# power.net
KiCad netlist of a schematic drawn in Altium Designer
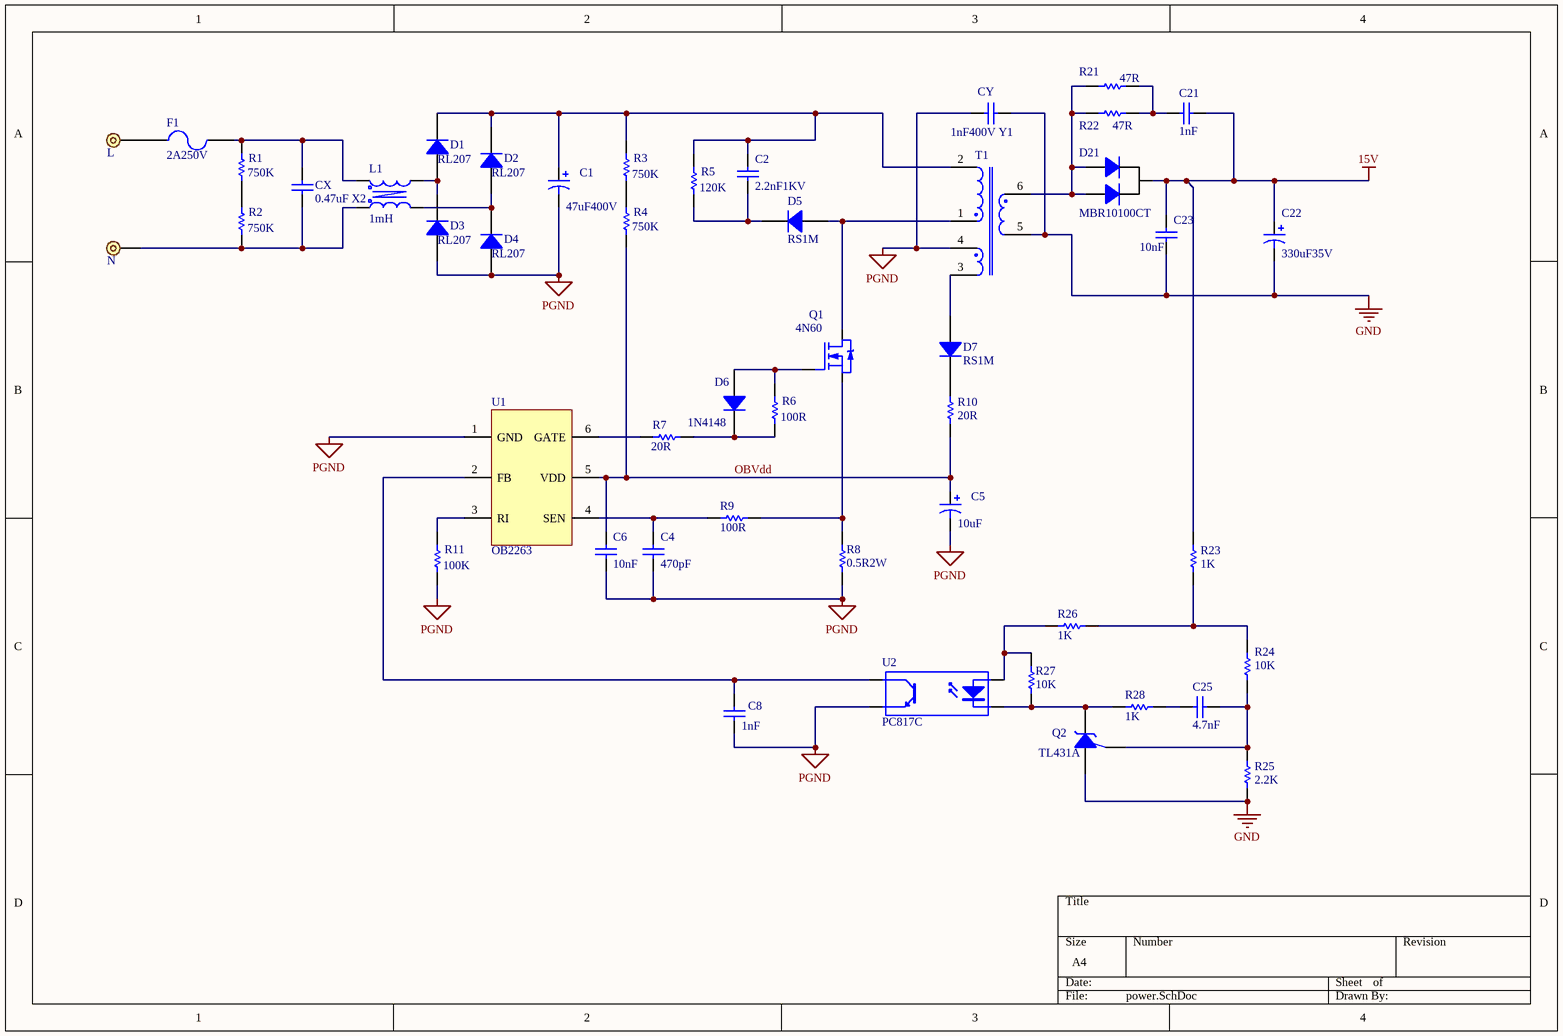
[diagram p0: power.SchDoc]

(export (version "E")
  (design (tool "Eeschema 10.0.6"))
  (components
    (comp (ref "C1")
      (value "47uF400V")
      (footprint "CAP16x25")
      (description "电解电容")
      (fields (field (name "PUBLISHER") "Altium Limited"))
      (libsource (lib "nizn") (part "Cap Pol2"))
    )
    (comp (ref "C2")
      (value "2.2nF1KV")
      (footprint "CAP5")
      (description "涤纶电容")
      (fields (field (name "Comment") "Cap") (field (name "PUBLISHER") "Altium Limited"))
      (libsource (lib "Miscellaneous Devices") (part "Cap"))
    )
    (comp (ref "C4")
      (value "470pF")
      (footprint "CAP0805")
      (description "贴片电容")
      (fields (field (name "Comment") "Cap") (field (name "PUBLISHER") "Altium Limited"))
      (libsource (lib "Miscellaneous Devices") (part "Cap"))
    )
    (comp (ref "C5")
      (value "10uF")
      (footprint "CAP3")
      (description "电解电容")
      (fields (field (name "PUBLISHER") "Altium Limited"))
      (libsource (lib "nizn") (part "Cap Pol2"))
    )
    (comp (ref "C6")
      (value "10nF")
      (footprint "CAP0805")
      (description "贴片电容")
      (fields (field (name "Comment") "Cap") (field (name "PUBLISHER") "Altium Limited"))
      (libsource (lib "Miscellaneous Devices") (part "Cap"))
    )
    (comp (ref "C8")
      (value "1nF")
      (footprint "CAP0805")
      (description "贴片电容")
      (fields (field (name "Comment") "Cap") (field (name "PUBLISHER") "Altium Limited"))
      (libsource (lib "Miscellaneous Devices") (part "Cap"))
    )
    (comp (ref "C21")
      (value "1nF")
      (footprint "CAP1206")
      (description "贴片电容")
      (fields (field (name "Comment") "Cap") (field (name "PUBLISHER") "Altium Limited"))
      (libsource (lib "Miscellaneous Devices") (part "Cap"))
    )
    (comp (ref "C22")
      (value "330uF35V")
      (footprint "CAP10X16")
      (description "电解电容")
      (fields (field (name "PUBLISHER") "Altium Limited"))
      (libsource (lib "nizn") (part "Cap Pol2"))
    )
    (comp (ref "C23")
      (value "10nF")
      (footprint "CAP0805")
      (description "贴片电容")
      (fields (field (name "Comment") "Cap") (field (name "PUBLISHER") "Altium Limited"))
      (libsource (lib "Miscellaneous Devices") (part "Cap"))
    )
    (comp (ref "C25")
      (value "4.7nF")
      (footprint "CAP0805")
      (description "贴片电容")
      (fields (field (name "Comment") "Cap") (field (name "PUBLISHER") "Altium Limited"))
      (libsource (lib "Miscellaneous Devices") (part "Cap"))
    )
    (comp (ref "CX")
      (value "0.47uF X2")
      (footprint "CAPX2")
      (description "X2 安规电容")
      (fields (field (name "Comment") "Cap") (field (name "PUBLISHER") "Altium Limited"))
      (libsource (lib "Miscellaneous Devices") (part "Cap"))
    )
    (comp (ref "CY")
      (value "1nF400V Y1")
      (footprint "CAPY2")
      (description "Y2 安规电容")
      (fields (field (name "Comment") "Cap") (field (name "PUBLISHER") "Altium Limited"))
      (libsource (lib "Miscellaneous Devices") (part "Cap"))
    )
    (comp (ref "D1")
      (value "RL207")
      (footprint "DIO10mm")
      (description "直插二极管")
      (fields (field (name "PUBLISHER") "Altium Limited"))
      (libsource (lib "nizn") (part "Diode"))
    )
    (comp (ref "D2")
      (value "RL207")
      (footprint "DIO10mm")
      (description "直插二极管")
      (fields (field (name "PUBLISHER") "Altium Limited"))
      (libsource (lib "nizn") (part "Diode"))
    )
    (comp (ref "D3")
      (value "RL207")
      (footprint "DIO10mm")
      (description "直插二极管")
      (fields (field (name "PUBLISHER") "Altium Limited"))
      (libsource (lib "nizn") (part "Diode"))
    )
    (comp (ref "D4")
      (value "RL207")
      (footprint "DIO10mm")
      (description "直插二极管")
      (fields (field (name "PUBLISHER") "Altium Limited"))
      (libsource (lib "nizn") (part "Diode"))
    )
    (comp (ref "D5")
      (value "RS1M")
      (footprint "DO214A")
      (description "贴片二极管")
      (fields (field (name "PUBLISHER") "Altium Limited"))
      (libsource (lib "nizn") (part "Diode"))
    )
    (comp (ref "D6")
      (value "1N4148")
      (footprint "1N4148SMT")
      (description "贴片二极管")
      (fields (field (name "PUBLISHER") "Altium Limited"))
      (libsource (lib "nizn") (part "Diode"))
    )
    (comp (ref "D7")
      (value "RS1M")
      (footprint "DO214A")
      (description "贴片二极管")
      (fields (field (name "PUBLISHER") "Altium Limited"))
      (libsource (lib "nizn") (part "Diode"))
    )
    (comp (ref "D21")
      (value "MBR10100CT")
      (footprint "TO220DIO_HS")
      (description "整流双二极管")
      (fields (field (name "PUBLISHER") "Altium Limited"))
      (libsource (lib "nizn") (part "Diode2"))
    )
    (comp (ref "F1")
      (value "2A250V")
      (footprint "FUSE3X10_2")
      (description "直插保险丝")
      (fields (field (name "PUBLISHER") "Altium Limited"))
      (libsource (lib "nizn") (part "Fuse 2"))
    )
    (comp (ref "J1")
      (value "L")
      (footprint "PAD1")
      (description "电源火线")
      (fields (field (name "PUBLISHER") "Altium Limited"))
      (libsource (lib "nizn") (part "Header1"))
    )
    (comp (ref "J2")
      (value "N")
      (footprint "PAD1")
      (description "电源零线")
      (fields (field (name "PUBLISHER") "Altium Limited"))
      (libsource (lib "nizn") (part "Header1"))
    )
    (comp (ref "L1")
      (value "1mH")
      (footprint "BU10")
      (description "共模电感")
      (libsource (lib "nizn") (part "TRANS3"))
    )
    (comp (ref "Q1")
      (value "4N60")
      (footprint "TO220MOS_HS")
      (description "高压 NMOS")
      (fields (field (name "PUBLISHER") "Altium Limited"))
      (libsource (lib "nizn") (part "NMOS"))
    )
    (comp (ref "Q2")
      (value "TL431A")
      (footprint "SOT23_431")
      (description "基准集成电路")
      (fields (field (name "PUBLISHER") "Altium Limited"))
      (libsource (lib "nizn") (part "TL431"))
    )
    (comp (ref "R1")
      (value "750K")
      (footprint "RES1206")
      (description "贴片电阻")
      (fields (field (name "Comment") "Res1") (field (name "PUBLISHER") "Altium Limited"))
      (libsource (lib "Miscellaneous Devices") (part "Res1"))
    )
    (comp (ref "R2")
      (value "750K")
      (footprint "RES1206")
      (description "贴片电阻")
      (fields (field (name "Comment") "Res1") (field (name "PUBLISHER") "Altium Limited"))
      (libsource (lib "Miscellaneous Devices") (part "Res1"))
    )
    (comp (ref "R3")
      (value "750K")
      (footprint "RES1206")
      (description "贴片电阻")
      (fields (field (name "Comment") "Res1") (field (name "PUBLISHER") "Altium Limited"))
      (libsource (lib "Miscellaneous Devices") (part "Res1"))
    )
    (comp (ref "R4")
      (value "750K")
      (footprint "RES1206")
      (description "贴片电阻")
      (fields (field (name "Comment") "Res1") (field (name "PUBLISHER") "Altium Limited"))
      (libsource (lib "Miscellaneous Devices") (part "Res1"))
    )
    (comp (ref "R5")
      (value "120K")
      (footprint "RES1206")
      (description "贴片电阻")
      (fields (field (name "Comment") "Res1") (field (name "PUBLISHER") "Altium Limited"))
      (libsource (lib "Miscellaneous Devices") (part "Res1"))
    )
    (comp (ref "R6")
      (value "100R")
      (footprint "RES0805")
      (description "贴片电阻")
      (fields (field (name "Comment") "Res1") (field (name "PUBLISHER") "Altium Limited"))
      (libsource (lib "Miscellaneous Devices") (part "Res1"))
    )
    (comp (ref "R7")
      (value "20R")
      (footprint "RES0805")
      (description "贴片电阻")
      (fields (field (name "Comment") "Res1") (field (name "PUBLISHER") "Altium Limited"))
      (libsource (lib "Miscellaneous Devices") (part "Res1"))
    )
    (comp (ref "R8")
      (value "0.5R2W")
      (footprint "RES2W")
      (description "2W 直插电阻")
      (fields (field (name "Comment") "Res1") (field (name "PUBLISHER") "Altium Limited"))
      (libsource (lib "Miscellaneous Devices") (part "Res1"))
    )
    (comp (ref "R9")
      (value "100R")
      (footprint "RES0805")
      (description "贴片电阻")
      (fields (field (name "Comment") "Res1") (field (name "PUBLISHER") "Altium Limited"))
      (libsource (lib "Miscellaneous Devices") (part "Res1"))
    )
    (comp (ref "R10")
      (value "20R")
      (footprint "RES1206")
      (description "贴片电阻")
      (fields (field (name "Comment") "Res1") (field (name "PUBLISHER") "Altium Limited"))
      (libsource (lib "Miscellaneous Devices") (part "Res1"))
    )
    (comp (ref "R11")
      (value "100K")
      (footprint "RES0805")
      (description "贴片电阻")
      (fields (field (name "Comment") "Res1") (field (name "PUBLISHER") "Altium Limited"))
      (libsource (lib "Miscellaneous Devices") (part "Res1"))
    )
    (comp (ref "R21")
      (value "47R")
      (footprint "RES1206")
      (description "贴片电阻")
      (fields (field (name "Comment") "Res1") (field (name "PUBLISHER") "Altium Limited"))
      (libsource (lib "Miscellaneous Devices") (part "Res1"))
    )
    (comp (ref "R22")
      (value "47R")
      (footprint "RES1206")
      (description "贴片电阻")
      (fields (field (name "Comment") "Res1") (field (name "PUBLISHER") "Altium Limited"))
      (libsource (lib "Miscellaneous Devices") (part "Res1"))
    )
    (comp (ref "R23")
      (value "1K")
      (footprint "RES0805")
      (description "贴片电阻")
      (fields (field (name "Comment") "Res1") (field (name "PUBLISHER") "Altium Limited"))
      (libsource (lib "Miscellaneous Devices") (part "Res1"))
    )
    (comp (ref "R24")
      (value "10K")
      (footprint "RES0805")
      (description "贴片电阻")
      (fields (field (name "Comment") "Res1") (field (name "PUBLISHER") "Altium Limited"))
      (libsource (lib "Miscellaneous Devices") (part "Res1"))
    )
    (comp (ref "R25")
      (value "2.2K")
      (footprint "RES0805")
      (description "贴片电阻")
      (fields (field (name "Comment") "Res1") (field (name "PUBLISHER") "Altium Limited"))
      (libsource (lib "Miscellaneous Devices") (part "Res1"))
    )
    (comp (ref "R26")
      (value "1K")
      (footprint "RES0805")
      (description "贴片电阻")
      (fields (field (name "Comment") "Res1") (field (name "PUBLISHER") "Altium Limited"))
      (libsource (lib "Miscellaneous Devices") (part "Res1"))
    )
    (comp (ref "R27")
      (value "10K")
      (footprint "RES0805")
      (description "贴片电阻")
      (fields (field (name "Comment") "Res1") (field (name "PUBLISHER") "Altium Limited"))
      (libsource (lib "Miscellaneous Devices") (part "Res1"))
    )
    (comp (ref "R28")
      (value "1K")
      (footprint "RES0805")
      (description "贴片电阻")
      (fields (field (name "Comment") "Res1") (field (name "PUBLISHER") "Altium Limited"))
      (libsource (lib "Miscellaneous Devices") (part "Res1"))
    )
    (comp (ref "T1")
      (value "Transformer")
      (footprint "PQ20C1")
      (description "变压器")
      (fields (field (name "PUBLISHER") "Altium Limited"))
      (libsource (lib "nizn") (part "PQ20C1"))
    )
    (comp (ref "U1")
      (value "OB2263")
      (footprint "SOT23-6")
      (description "集成电路")
      (libsource (lib "nizn") (part "OB2263"))
    )
    (comp (ref "U2")
      (value "PC817C")
      (footprint "DIP-4")
      (description "光耦")
      (fields (field (name "PUBLISHER") "Altium Limited"))
      (libsource (lib "nizn") (part "Optoisolator1"))
    )
  )
  (nets
    (net (code "1") (name "/OBVdd") (class "Default")
      (node (ref "C5") (pin "1") (pinfunction "1_1") (pintype "passive"))
      (node (ref "C6") (pin "2") (pinfunction "2_2") (pintype "passive"))
      (node (ref "R10") (pin "2") (pinfunction "2_2") (pintype "passive"))
      (node (ref "R4") (pin "1") (pinfunction "1_1") (pintype "passive"))
      (node (ref "U1") (pin "5") (pinfunction "VDD_5") (pintype "passive"))
    )
    (net (code "2") (name "15V") (class "Default")
      (node (ref "C21") (pin "1") (pinfunction "1_1") (pintype "passive"))
      (node (ref "C22") (pin "1") (pinfunction "1_1") (pintype "passive"))
      (node (ref "C23") (pin "2") (pinfunction "2_2") (pintype "passive"))
      (node (ref "D21") (pin "2") (pinfunction "K_2") (pintype "passive"))
      (node (ref "R23") (pin "1") (pinfunction "1_1") (pintype "passive"))
    )
    (net (code "3") (name "GND") (class "Default")
      (node (ref "C22") (pin "2") (pinfunction "2_2") (pintype "passive"))
      (node (ref "C23") (pin "1") (pinfunction "1_1") (pintype "passive"))
      (node (ref "CY") (pin "1") (pinfunction "1_1") (pintype "passive"))
      (node (ref "Q2") (pin "2") (pinfunction "A_2") (pintype "passive"))
      (node (ref "R25") (pin "1") (pinfunction "1_1") (pintype "passive"))
      (node (ref "T1") (pin "5") (pinfunction "5_5") (pintype "passive"))
    )
    (net (code "4") (name "Net-(C21-Pad2)") (class "Default")
      (node (ref "C21") (pin "2") (pinfunction "2_2") (pintype "passive"))
      (node (ref "R21") (pin "1") (pinfunction "1_1") (pintype "passive"))
      (node (ref "R22") (pin "1") (pinfunction "1_1") (pintype "passive"))
    )
    (net (code "5") (name "Net-(C25-Pad2)") (class "Default")
      (node (ref "C25") (pin "2") (pinfunction "2_2") (pintype "passive"))
      (node (ref "R28") (pin "1") (pinfunction "1_1") (pintype "passive"))
    )
    (net (code "6") (name "Net-(CX-Pad1)") (class "Default")
      (node (ref "CX") (pin "1") (pinfunction "1_1") (pintype "passive"))
      (node (ref "J2") (pin "1") (pinfunction "1_1") (pintype "passive"))
      (node (ref "L1") (pin "4") (pinfunction "4_4") (pintype "passive"))
      (node (ref "R2") (pin "1") (pinfunction "1_1") (pintype "passive"))
    )
    (net (code "7") (name "Net-(CX-Pad2)") (class "Default")
      (node (ref "CX") (pin "2") (pinfunction "2_2") (pintype "passive"))
      (node (ref "F1") (pin "2") (pinfunction "2_2") (pintype "passive"))
      (node (ref "L1") (pin "1") (pinfunction "1_1") (pintype "passive"))
      (node (ref "R1") (pin "2") (pinfunction "2_2") (pintype "passive"))
    )
    (net (code "8") (name "Net-(D1-A)") (class "Default")
      (node (ref "D1") (pin "1") (pinfunction "A_1") (pintype "passive"))
      (node (ref "D3") (pin "2") (pinfunction "K_2") (pintype "passive"))
      (node (ref "L1") (pin "2") (pinfunction "2_2") (pintype "passive"))
    )
    (net (code "9") (name "Net-(D1-K)") (class "Default")
      (node (ref "C1") (pin "1") (pinfunction "1_1") (pintype "passive"))
      (node (ref "C2") (pin "2") (pinfunction "2_2") (pintype "passive"))
      (node (ref "D1") (pin "2") (pinfunction "K_2") (pintype "passive"))
      (node (ref "D2") (pin "2") (pinfunction "K_2") (pintype "passive"))
      (node (ref "R3") (pin "2") (pinfunction "2_2") (pintype "passive"))
      (node (ref "R5") (pin "2") (pinfunction "2_2") (pintype "passive"))
      (node (ref "T1") (pin "2") (pinfunction "2_2") (pintype "passive"))
    )
    (net (code "10") (name "Net-(D2-A)") (class "Default")
      (node (ref "D2") (pin "1") (pinfunction "A_1") (pintype "passive"))
      (node (ref "D4") (pin "2") (pinfunction "K_2") (pintype "passive"))
      (node (ref "L1") (pin "3") (pinfunction "3_3") (pintype "passive"))
    )
    (net (code "11") (name "Net-(D5-A)") (class "Default")
      (node (ref "D5") (pin "1") (pinfunction "A_1") (pintype "passive"))
      (node (ref "Q1") (pin "D") (pinfunction "D_D") (pintype "passive"))
      (node (ref "T1") (pin "1") (pinfunction "1_1") (pintype "passive"))
    )
    (net (code "12") (name "Net-(D5-K)") (class "Default")
      (node (ref "C2") (pin "1") (pinfunction "1_1") (pintype "passive"))
      (node (ref "D5") (pin "2") (pinfunction "K_2") (pintype "passive"))
      (node (ref "R5") (pin "1") (pinfunction "1_1") (pintype "passive"))
    )
    (net (code "13") (name "Net-(D6-A)") (class "Default")
      (node (ref "D6") (pin "1") (pinfunction "A_1") (pintype "passive"))
      (node (ref "Q1") (pin "G") (pinfunction "G_G") (pintype "passive"))
      (node (ref "R6") (pin "2") (pinfunction "2_2") (pintype "passive"))
    )
    (net (code "14") (name "Net-(D6-K)") (class "Default")
      (node (ref "D6") (pin "2") (pinfunction "K_2") (pintype "passive"))
      (node (ref "R6") (pin "1") (pinfunction "1_1") (pintype "passive"))
      (node (ref "R7") (pin "1") (pinfunction "1_1") (pintype "passive"))
    )
    (net (code "15") (name "Net-(D7-A)") (class "Default")
      (node (ref "D7") (pin "1") (pinfunction "A_1") (pintype "passive"))
      (node (ref "T1") (pin "3") (pinfunction "3_3") (pintype "passive"))
    )
    (net (code "16") (name "Net-(D7-K)") (class "Default")
      (node (ref "D7") (pin "2") (pinfunction "K_2") (pintype "passive"))
      (node (ref "R10") (pin "1") (pinfunction "1_1") (pintype "passive"))
    )
    (net (code "17") (name "Net-(D21-A-Pad1)") (class "Default")
      (node (ref "D21") (pin "1") (pinfunction "A_1") (pintype "passive"))
      (node (ref "D21") (pin "3") (pinfunction "A_3") (pintype "passive"))
      (node (ref "R21") (pin "2") (pinfunction "2_2") (pintype "passive"))
      (node (ref "R22") (pin "2") (pinfunction "2_2") (pintype "passive"))
      (node (ref "T1") (pin "6") (pinfunction "6_6") (pintype "passive"))
    )
    (net (code "18") (name "Net-(F1-Pad1)") (class "Default")
      (node (ref "F1") (pin "1") (pinfunction "1_1") (pintype "passive"))
      (node (ref "J1") (pin "1") (pinfunction "1_1") (pintype "passive"))
    )
    (net (code "19") (name "Net-(Q1-PadS)") (class "Default")
      (node (ref "Q1") (pin "S") (pinfunction "S_S") (pintype "passive"))
      (node (ref "R8") (pin "1") (pinfunction "1_1") (pintype "passive"))
      (node (ref "R9") (pin "1") (pinfunction "1_1") (pintype "passive"))
    )
    (net (code "20") (name "Net-(Q2-C)") (class "Default")
      (node (ref "Q2") (pin "3") (pinfunction "C_3") (pintype "passive"))
      (node (ref "R27") (pin "1") (pinfunction "1_1") (pintype "passive"))
      (node (ref "R28") (pin "2") (pinfunction "2_2") (pintype "passive"))
      (node (ref "U2") (pin "2") (pinfunction "K_2") (pintype "passive"))
    )
    (net (code "21") (name "Net-(Q2-R)") (class "Default")
      (node (ref "C25") (pin "1") (pinfunction "1_1") (pintype "passive"))
      (node (ref "Q2") (pin "1") (pinfunction "R_1") (pintype "passive"))
      (node (ref "R24") (pin "1") (pinfunction "1_1") (pintype "passive"))
      (node (ref "R25") (pin "2") (pinfunction "2_2") (pintype "passive"))
    )
    (net (code "22") (name "Net-(R1-Pad1)") (class "Default")
      (node (ref "R1") (pin "1") (pinfunction "1_1") (pintype "passive"))
      (node (ref "R2") (pin "2") (pinfunction "2_2") (pintype "passive"))
    )
    (net (code "23") (name "Net-(R3-Pad1)") (class "Default")
      (node (ref "R3") (pin "1") (pinfunction "1_1") (pintype "passive"))
      (node (ref "R4") (pin "2") (pinfunction "2_2") (pintype "passive"))
    )
    (net (code "24") (name "Net-(R23-Pad2)") (class "Default")
      (node (ref "R23") (pin "2") (pinfunction "2_2") (pintype "passive"))
      (node (ref "R24") (pin "2") (pinfunction "2_2") (pintype "passive"))
      (node (ref "R26") (pin "2") (pinfunction "2_2") (pintype "passive"))
    )
    (net (code "25") (name "Net-(U1-FB)") (class "Default")
      (node (ref "C8") (pin "2") (pinfunction "2_2") (pintype "passive"))
      (node (ref "U1") (pin "2") (pinfunction "FB_2") (pintype "passive"))
      (node (ref "U2") (pin "4") (pinfunction "C_4") (pintype "passive"))
    )
    (net (code "26") (name "Net-(U1-GATE)") (class "Default")
      (node (ref "R7") (pin "2") (pinfunction "2_2") (pintype "passive"))
      (node (ref "U1") (pin "6") (pinfunction "GATE_6") (pintype "passive"))
    )
    (net (code "27") (name "Net-(U1-RI)") (class "Default")
      (node (ref "R11") (pin "2") (pinfunction "2_2") (pintype "passive"))
      (node (ref "U1") (pin "3") (pinfunction "RI_3") (pintype "passive"))
    )
    (net (code "28") (name "Net-(U1-SEN)") (class "Default")
      (node (ref "C4") (pin "2") (pinfunction "2_2") (pintype "passive"))
      (node (ref "R9") (pin "2") (pinfunction "2_2") (pintype "passive"))
      (node (ref "U1") (pin "4") (pinfunction "SEN_4") (pintype "passive"))
    )
    (net (code "29") (name "Net-(U2-A)") (class "Default")
      (node (ref "R26") (pin "1") (pinfunction "1_1") (pintype "passive"))
      (node (ref "R27") (pin "2") (pinfunction "2_2") (pintype "passive"))
      (node (ref "U2") (pin "1") (pinfunction "A_1") (pintype "passive"))
    )
    (net (code "30") (name "PGND") (class "Default")
      (node (ref "C1") (pin "2") (pinfunction "2_2") (pintype "passive"))
      (node (ref "C4") (pin "1") (pinfunction "1_1") (pintype "passive"))
      (node (ref "C5") (pin "2") (pinfunction "2_2") (pintype "passive"))
      (node (ref "C6") (pin "1") (pinfunction "1_1") (pintype "passive"))
      (node (ref "C8") (pin "1") (pinfunction "1_1") (pintype "passive"))
      (node (ref "CY") (pin "2") (pinfunction "2_2") (pintype "passive"))
      (node (ref "D3") (pin "1") (pinfunction "A_1") (pintype "passive"))
      (node (ref "D4") (pin "1") (pinfunction "A_1") (pintype "passive"))
      (node (ref "R11") (pin "1") (pinfunction "1_1") (pintype "passive"))
      (node (ref "R8") (pin "2") (pinfunction "2_2") (pintype "passive"))
      (node (ref "T1") (pin "4") (pinfunction "4_4") (pintype "passive"))
      (node (ref "U1") (pin "1") (pinfunction "GND_1") (pintype "passive"))
      (node (ref "U2") (pin "3") (pinfunction "E_3") (pintype "passive"))
    )
  )
)
